# EFM32_G11_MCU.net
KiCad netlist of a schematic drawn in Altium Designer
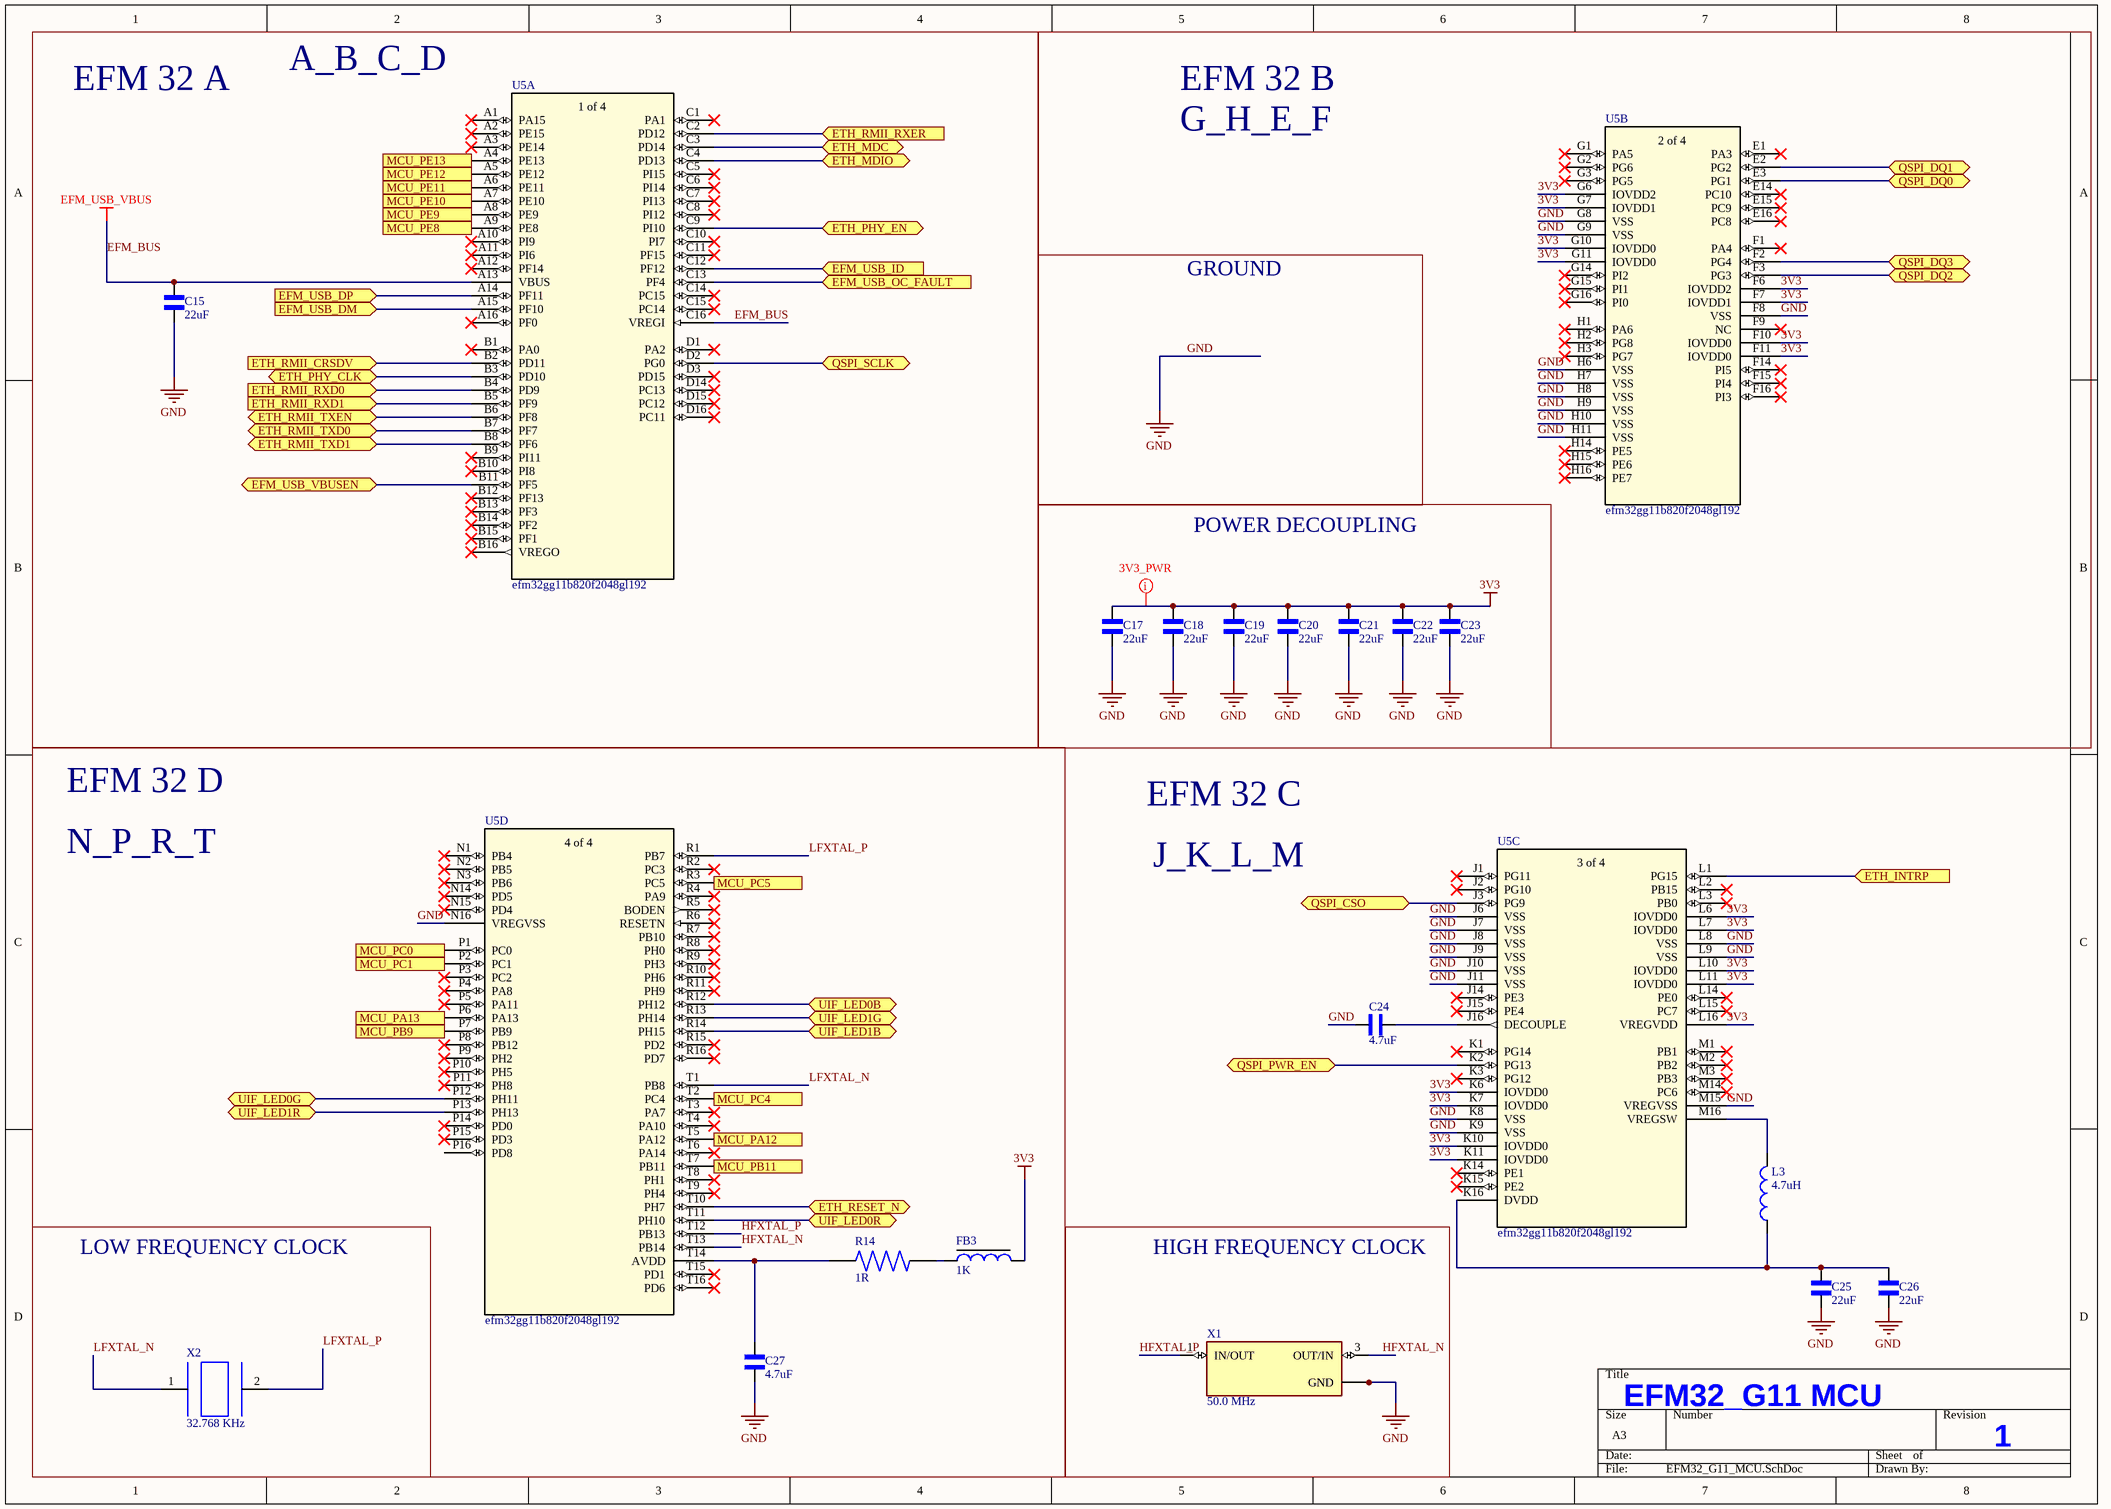
[diagram p0: EFM32_G11_MCU.SchDoc]

(export (version "E")
  (design (tool "Eeschema 10.0.6"))
  (components
    (comp (ref "C15")
      (value "22uF")
      (footprint "C0603")
      (description "0603 22 uF 10 V ±20% Tolerance X5R Surface Mount Multilayer Ceramic Capacitor")
      (fields
        (field (name "MANUFACTURER") "Murata")
        (field (name "MANUFACTURER PART NUMBER") "ZRB18AR61A226ME01L")
      )
      (libsource (lib "") (part "ZRB18AR61A226ME01L_1"))
    )
    (comp (ref "C17")
      (value "22uF")
      (footprint "C0603")
      (description "0603 22 uF 10 V ±20% Tolerance X5R Surface Mount Multilayer Ceramic Capacitor")
      (fields
        (field (name "MANUFACTURER") "Murata")
        (field (name "MANUFACTURER PART NUMBER") "ZRB18AR61A226ME01L")
      )
      (libsource (lib "") (part "ZRB18AR61A226ME01L_1"))
    )
    (comp (ref "C18")
      (value "22uF")
      (footprint "C0603")
      (description "0603 22 uF 10 V ±20% Tolerance X5R Surface Mount Multilayer Ceramic Capacitor")
      (fields
        (field (name "MANUFACTURER") "Murata")
        (field (name "MANUFACTURER PART NUMBER") "ZRB18AR61A226ME01L")
      )
      (libsource (lib "") (part "ZRB18AR61A226ME01L_1"))
    )
    (comp (ref "C19")
      (value "22uF")
      (footprint "C0603")
      (description "0603 22 uF 10 V ±20% Tolerance X5R Surface Mount Multilayer Ceramic Capacitor")
      (fields
        (field (name "MANUFACTURER") "Murata")
        (field (name "MANUFACTURER PART NUMBER") "ZRB18AR61A226ME01L")
      )
      (libsource (lib "nnts") (part "ZRB18AR61A226ME01L"))
    )
    (comp (ref "C20")
      (value "22uF")
      (footprint "C0603")
      (description "0603 22 uF 10 V ±20% Tolerance X5R Surface Mount Multilayer Ceramic Capacitor")
      (fields
        (field (name "MANUFACTURER") "Murata")
        (field (name "MANUFACTURER PART NUMBER") "ZRB18AR61A226ME01L")
      )
      (libsource (lib "nnts") (part "ZRB18AR61A226ME01L"))
    )
    (comp (ref "C21")
      (value "22uF")
      (footprint "C0603")
      (description "0603 22 uF 10 V ±20% Tolerance X5R Surface Mount Multilayer Ceramic Capacitor")
      (fields
        (field (name "MANUFACTURER") "Murata")
        (field (name "MANUFACTURER PART NUMBER") "ZRB18AR61A226ME01L")
      )
      (libsource (lib "nnts") (part "ZRB18AR61A226ME01L"))
    )
    (comp (ref "C22")
      (value "22uF")
      (footprint "C0603")
      (description "0603 22 uF 10 V ±20% Tolerance X5R Surface Mount Multilayer Ceramic Capacitor")
      (fields
        (field (name "MANUFACTURER") "Murata")
        (field (name "MANUFACTURER PART NUMBER") "ZRB18AR61A226ME01L")
      )
      (libsource (lib "nnts") (part "ZRB18AR61A226ME01L"))
    )
    (comp (ref "C23")
      (value "22uF")
      (footprint "C0603")
      (description "0603 22 uF 10 V ±20% Tolerance X5R Surface Mount Multilayer Ceramic Capacitor")
      (fields
        (field (name "MANUFACTURER") "Murata")
        (field (name "MANUFACTURER PART NUMBER") "ZRB18AR61A226ME01L")
      )
      (libsource (lib "nnts") (part "ZRB18AR61A226ME01L"))
    )
    (comp (ref "C24")
      (value "4.7uF")
      (footprint "C0603")
      (description "Cap Ceramic 4.7uF 10V X5R 10% Pad SMD 0603 85C T/R")
      (fields
        (field (name "MANUFACTURER") "Samsung")
        (field (name "MANUFACTURER PART NUMBER") "CL10A475KP8NNNC")
      )
      (libsource (lib "nnts") (part "CL10A475KP8NNNC"))
    )
    (comp (ref "C25")
      (value "22uF")
      (footprint "C0603")
      (description "0603 22 uF 10 V ±20% Tolerance X5R Surface Mount Multilayer Ceramic Capacitor")
      (fields
        (field (name "MANUFACTURER") "Murata")
        (field (name "MANUFACTURER PART NUMBER") "ZRB18AR61A226ME01L")
      )
      (libsource (lib "nnts") (part "ZRB18AR61A226ME01L"))
    )
    (comp (ref "C26")
      (value "22uF")
      (footprint "C0603")
      (description "0603 22 uF 10 V ±20% Tolerance X5R Surface Mount Multilayer Ceramic Capacitor")
      (fields
        (field (name "MANUFACTURER") "Murata")
        (field (name "MANUFACTURER PART NUMBER") "ZRB18AR61A226ME01L")
      )
      (libsource (lib "nnts") (part "ZRB18AR61A226ME01L"))
    )
    (comp (ref "C27")
      (value "4.7uF")
      (footprint "C0603")
      (description "Cap Ceramic 4.7uF 10V X5R 10% Pad SMD 0603 85C T/R")
      (fields
        (field (name "MANUFACTURER") "Samsung")
        (field (name "MANUFACTURER PART NUMBER") "CL10A475KP8NNNC")
      )
      (libsource (lib "") (part "CL10A475KP8NNNC_1"))
    )
    (comp (ref "FB3")
      (value "1K")
      (footprint "FB0402")
      (description "FERRITE BEAD 1 KOHM 0402 1LN")
      (fields
        (field (name "MANUFACTURER") "Murata")
        (field (name "MANUFACTURER PART NUMBER") "BLM15AG102SH1D")
      )
      (libsource (lib "nnts") (part "BLM15AG102SH1D"))
    )
    (comp (ref "L3")
      (value "4.7uH")
      (footprint "L0805")
      (description "Inductor with Inductance: 4.7uH Tol. +/-20%, Package: 0805 (2012)")
      (fields (field (name "MP") "LQM21PN4R7MGRB") (field (name "MF") "Murata"))
      (libsource (lib "nnts") (part "LQM21PN4R7MGRB"))
    )
    (comp (ref "R14")
      (value "1R")
      (footprint "R0402 Vishay")
      (description "RES SMD 1 OHM 1% 1/16W 0402")
      (fields
        (field (name "MANUFACTURER") "Vishay")
        (field (name "MANUFACTURER PART NUMBER") "CRCW04021R00FNED")
      )
      (libsource (lib "nnts") (part "CRCW04021R00FNED"))
    )
    (comp (ref "U5")
      (value "efm32gg11b820f2048gl192")
      (footprint "MCU_GG11")
      (description "No Description Available")
      (fields (field (name "COPYRIGHT") "Copyright (C) 2016 Accelerated Designs. All rights reserved"))
      (libsource (lib "nnts") (part "EFM32GG11B820F20"))
    )
    (comp (ref "X1")
      (value "50.0 MHz")
      (footprint "XTAL_ECS-500-8-47B-CWY-TR")
      (description "CRYSTAL 50.0000MHZ 8PF SMD")
      (fields (field (name "MF") "ECS Inc.") (field (name "MP") "ECS-500-8-47B-CWY-TR"))
      (libsource (lib "nnts") (part "ECS-500-8-47B-CWY-TR"))
    )
    (comp (ref "X2")
      (value "32.768 KHz")
      (footprint "XTAL_FC-135_32.7680KA-A0")
      (description "32.768kHz Â±20ppm Crystal 12.5pF 70 kOhms 2-SMD, No Lead")
      (fields (field (name "MP") "FC-135 32.7680KA-A0") (field (name "MF") "EPSON"))
      (libsource (lib "nnts") (part "FC-135_32.7680KA-A0"))
    )
  )
  (nets
    (net (code "1") (name "/EFM_USB_DM") (class "Default")
      (node (ref "U5") (pin "A15") (pinfunction "PF10_A15") (pintype "bidirectional"))
    )
    (net (code "2") (name "/EFM_USB_DP") (class "Default")
      (node (ref "U5") (pin "A14") (pinfunction "PF11_A14") (pintype "bidirectional"))
    )
    (net (code "3") (name "/EFM_USB_ID") (class "Default")
      (node (ref "U5") (pin "C12") (pinfunction "PF12_C12") (pintype "bidirectional"))
    )
    (net (code "4") (name "/EFM_USB_OC_FAULT") (class "Default")
      (node (ref "U5") (pin "C13") (pinfunction "PF4_C13") (pintype "bidirectional"))
    )
    (net (code "5") (name "/EFM_USB_VBUSEN") (class "Default")
      (node (ref "U5") (pin "B11") (pinfunction "PF5_B11") (pintype "bidirectional"))
    )
    (net (code "6") (name "/ETH_INTRP") (class "Default")
      (node (ref "U5") (pin "L1") (pinfunction "PG15_L1") (pintype "bidirectional"))
    )
    (net (code "7") (name "/ETH_MDC") (class "Default")
      (node (ref "U5") (pin "C3") (pinfunction "PD14_C3") (pintype "bidirectional"))
    )
    (net (code "8") (name "/ETH_MDIO") (class "Default")
      (node (ref "U5") (pin "C4") (pinfunction "PD13_C4") (pintype "bidirectional"))
    )
    (net (code "9") (name "/ETH_PHY_CLK") (class "Default")
      (node (ref "U5") (pin "B3") (pinfunction "PD10_B3") (pintype "bidirectional"))
    )
    (net (code "10") (name "/ETH_PHY_EN") (class "Default")
      (node (ref "U5") (pin "C9") (pinfunction "PI10_C9") (pintype "bidirectional"))
    )
    (net (code "11") (name "/ETH_RESET_N") (class "Default")
      (node (ref "U5") (pin "T10") (pinfunction "PH7_T10") (pintype "bidirectional"))
    )
    (net (code "12") (name "/ETH_RMII_CRSDV") (class "Default")
      (node (ref "U5") (pin "B2") (pinfunction "PD11_B2") (pintype "bidirectional"))
    )
    (net (code "13") (name "/ETH_RMII_RXD0") (class "Default")
      (node (ref "U5") (pin "B4") (pinfunction "PD9_B4") (pintype "bidirectional"))
    )
    (net (code "14") (name "/ETH_RMII_RXD1") (class "Default")
      (node (ref "U5") (pin "B5") (pinfunction "PF9_B5") (pintype "bidirectional"))
    )
    (net (code "15") (name "/ETH_RMII_RXER") (class "Default")
      (node (ref "U5") (pin "C2") (pinfunction "PD12_C2") (pintype "bidirectional"))
    )
    (net (code "16") (name "/ETH_RMII_TXD0") (class "Default")
      (node (ref "U5") (pin "B7") (pinfunction "PF7_B7") (pintype "bidirectional"))
    )
    (net (code "17") (name "/ETH_RMII_TXD1") (class "Default")
      (node (ref "U5") (pin "B8") (pinfunction "PF6_B8") (pintype "bidirectional"))
    )
    (net (code "18") (name "/ETH_RMII_TXEN") (class "Default")
      (node (ref "U5") (pin "B6") (pinfunction "PF8_B6") (pintype "bidirectional"))
    )
    (net (code "19") (name "/HFXTAL_N") (class "Default")
      (node (ref "U5") (pin "T13") (pinfunction "PB14_T13") (pintype "bidirectional"))
      (node (ref "X1") (pin "3") (pinfunction "OUT/IN_3") (pintype "bidirectional"))
    )
    (net (code "20") (name "/HFXTAL_P") (class "Default")
      (node (ref "U5") (pin "T12") (pinfunction "PB13_T12") (pintype "bidirectional"))
      (node (ref "X1") (pin "1") (pinfunction "IN/OUT_1") (pintype "bidirectional"))
    )
    (net (code "21") (name "/LFXTAL_N") (class "Default")
      (node (ref "U5") (pin "T1") (pinfunction "PB8_T1") (pintype "bidirectional"))
      (node (ref "X2") (pin "1") (pinfunction "1_1") (pintype "passive"))
    )
    (net (code "22") (name "/LFXTAL_P") (class "Default")
      (node (ref "U5") (pin "R1") (pinfunction "PB7_R1") (pintype "bidirectional"))
      (node (ref "X2") (pin "2") (pinfunction "2_2") (pintype "passive"))
    )
    (net (code "23") (name "/MCU_PA12") (class "Default")
      (node (ref "U5") (pin "T5") (pinfunction "PA12_T5") (pintype "bidirectional"))
    )
    (net (code "24") (name "/MCU_PA13") (class "Default")
      (node (ref "U5") (pin "P6") (pinfunction "PA13_P6") (pintype "bidirectional"))
    )
    (net (code "25") (name "/MCU_PB9") (class "Default")
      (node (ref "U5") (pin "P7") (pinfunction "PB9_P7") (pintype "bidirectional"))
    )
    (net (code "26") (name "/MCU_PB11") (class "Default")
      (node (ref "U5") (pin "T7") (pinfunction "PB11_T7") (pintype "bidirectional"))
    )
    (net (code "27") (name "/MCU_PC0") (class "Default")
      (node (ref "U5") (pin "P1") (pinfunction "PC0_P1") (pintype "bidirectional"))
    )
    (net (code "28") (name "/MCU_PC1") (class "Default")
      (node (ref "U5") (pin "P2") (pinfunction "PC1_P2") (pintype "bidirectional"))
    )
    (net (code "29") (name "/MCU_PC4") (class "Default")
      (node (ref "U5") (pin "T2") (pinfunction "PC4_T2") (pintype "bidirectional"))
    )
    (net (code "30") (name "/MCU_PC5") (class "Default")
      (node (ref "U5") (pin "R3") (pinfunction "PC5_R3") (pintype "bidirectional"))
    )
    (net (code "31") (name "/MCU_PE8") (class "Default")
      (node (ref "U5") (pin "A9") (pinfunction "PE8_A9") (pintype "bidirectional"))
    )
    (net (code "32") (name "/MCU_PE9") (class "Default")
      (node (ref "U5") (pin "A8") (pinfunction "PE9_A8") (pintype "bidirectional"))
    )
    (net (code "33") (name "/MCU_PE10") (class "Default")
      (node (ref "U5") (pin "A7") (pinfunction "PE10_A7") (pintype "bidirectional"))
    )
    (net (code "34") (name "/MCU_PE11") (class "Default")
      (node (ref "U5") (pin "A6") (pinfunction "PE11_A6") (pintype "bidirectional"))
    )
    (net (code "35") (name "/MCU_PE12") (class "Default")
      (node (ref "U5") (pin "A5") (pinfunction "PE12_A5") (pintype "bidirectional"))
    )
    (net (code "36") (name "/MCU_PE13") (class "Default")
      (node (ref "U5") (pin "A4") (pinfunction "PE13_A4") (pintype "bidirectional"))
    )
    (net (code "37") (name "/QSPI_CSO") (class "Default")
      (node (ref "U5") (pin "J3") (pinfunction "PG9_J3") (pintype "bidirectional"))
    )
    (net (code "38") (name "/QSPI_DQ0") (class "Default")
      (node (ref "U5") (pin "E3") (pinfunction "PG1_E3") (pintype "bidirectional"))
    )
    (net (code "39") (name "/QSPI_DQ1") (class "Default")
      (node (ref "U5") (pin "E2") (pinfunction "PG2_E2") (pintype "bidirectional"))
    )
    (net (code "40") (name "/QSPI_DQ2") (class "Default")
      (node (ref "U5") (pin "F3") (pinfunction "PG3_F3") (pintype "bidirectional"))
    )
    (net (code "41") (name "/QSPI_DQ3") (class "Default")
      (node (ref "U5") (pin "F2") (pinfunction "PG4_F2") (pintype "bidirectional"))
    )
    (net (code "42") (name "/QSPI_PWR_EN") (class "Default")
      (node (ref "U5") (pin "K2") (pinfunction "PG13_K2") (pintype "bidirectional"))
    )
    (net (code "43") (name "/QSPI_SCLK") (class "Default")
      (node (ref "U5") (pin "D2") (pinfunction "PG0_D2") (pintype "bidirectional"))
    )
    (net (code "44") (name "/UIF_LED0B") (class "Default")
      (node (ref "U5") (pin "R12") (pinfunction "PH12_R12") (pintype "bidirectional"))
    )
    (net (code "45") (name "/UIF_LED0G") (class "Default")
      (node (ref "U5") (pin "P12") (pinfunction "PH11_P12") (pintype "bidirectional"))
    )
    (net (code "46") (name "/UIF_LED0R") (class "Default")
      (node (ref "U5") (pin "T11") (pinfunction "PH10_T11") (pintype "bidirectional"))
    )
    (net (code "47") (name "/UIF_LED1B") (class "Default")
      (node (ref "U5") (pin "R14") (pinfunction "PH15_R14") (pintype "bidirectional"))
    )
    (net (code "48") (name "/UIF_LED1G") (class "Default")
      (node (ref "U5") (pin "R13") (pinfunction "PH14_R13") (pintype "bidirectional"))
    )
    (net (code "49") (name "/UIF_LED1R") (class "Default")
      (node (ref "U5") (pin "P13") (pinfunction "PH13_P13") (pintype "bidirectional"))
    )
    (net (code "50") (name "3V3") (class "Default")
      (node (ref "C17") (pin "2") (pinfunction "2_2") (pintype "passive"))
      (node (ref "C18") (pin "2") (pinfunction "2_2") (pintype "passive"))
      (node (ref "C19") (pin "1") (pinfunction "1_1") (pintype "passive"))
      (node (ref "C20") (pin "1") (pinfunction "1_1") (pintype "passive"))
      (node (ref "C21") (pin "1") (pinfunction "1_1") (pintype "passive"))
      (node (ref "C22") (pin "1") (pinfunction "1_1") (pintype "passive"))
      (node (ref "C23") (pin "1") (pinfunction "1_1") (pintype "passive"))
      (node (ref "FB3") (pin "2") (pinfunction "2_2") (pintype "passive"))
      (node (ref "U5") (pin "F10") (pinfunction "IOVDD0_F10") (pintype "power_in"))
      (node (ref "U5") (pin "F11") (pinfunction "IOVDD0_F11") (pintype "power_in"))
      (node (ref "U5") (pin "F6") (pinfunction "IOVDD2_F6") (pintype "power_in"))
      (node (ref "U5") (pin "F7") (pinfunction "IOVDD1_F7") (pintype "power_in"))
      (node (ref "U5") (pin "G10") (pinfunction "IOVDD0_G10") (pintype "power_in"))
      (node (ref "U5") (pin "G11") (pinfunction "IOVDD0_G11") (pintype "power_in"))
      (node (ref "U5") (pin "G6") (pinfunction "IOVDD2_G6") (pintype "power_in"))
      (node (ref "U5") (pin "G7") (pinfunction "IOVDD1_G7") (pintype "power_in"))
      (node (ref "U5") (pin "K10") (pinfunction "IOVDD0_K10") (pintype "power_in"))
      (node (ref "U5") (pin "K11") (pinfunction "IOVDD0_K11") (pintype "power_in"))
      (node (ref "U5") (pin "K6") (pinfunction "IOVDD0_K6") (pintype "power_in"))
      (node (ref "U5") (pin "K7") (pinfunction "IOVDD0_K7") (pintype "power_in"))
      (node (ref "U5") (pin "L10") (pinfunction "IOVDD0_L10") (pintype "power_in"))
      (node (ref "U5") (pin "L11") (pinfunction "IOVDD0_L11") (pintype "power_in"))
      (node (ref "U5") (pin "L16") (pinfunction "VREGVDD_L16") (pintype "power_in"))
      (node (ref "U5") (pin "L6") (pinfunction "IOVDD0_L6") (pintype "power_in"))
      (node (ref "U5") (pin "L7") (pinfunction "IOVDD0_L7") (pintype "power_in"))
    )
    (net (code "51") (name "EFM_USB_VBUS") (class "Default")
      (node (ref "C15") (pin "2") (pinfunction "2_2") (pintype "passive"))
      (node (ref "U5") (pin "A13") (pinfunction "VBUS_A13") (pintype "power_in"))
      (node (ref "U5") (pin "C16") (pinfunction "VREGI_C16") (pintype "input"))
    )
    (net (code "52") (name "GND") (class "Default")
      (node (ref "C15") (pin "1") (pinfunction "1_1") (pintype "passive"))
      (node (ref "C17") (pin "1") (pinfunction "1_1") (pintype "passive"))
      (node (ref "C18") (pin "1") (pinfunction "1_1") (pintype "passive"))
      (node (ref "C19") (pin "2") (pinfunction "2_2") (pintype "passive"))
      (node (ref "C20") (pin "2") (pinfunction "2_2") (pintype "passive"))
      (node (ref "C21") (pin "2") (pinfunction "2_2") (pintype "passive"))
      (node (ref "C22") (pin "2") (pinfunction "2_2") (pintype "passive"))
      (node (ref "C23") (pin "2") (pinfunction "2_2") (pintype "passive"))
      (node (ref "C24") (pin "1") (pinfunction "1_1") (pintype "passive"))
      (node (ref "C25") (pin "2") (pinfunction "2_2") (pintype "passive"))
      (node (ref "C26") (pin "2") (pinfunction "2_2") (pintype "passive"))
      (node (ref "C27") (pin "1") (pinfunction "1_1") (pintype "passive"))
      (node (ref "U5") (pin "F8") (pinfunction "VSS_F8") (pintype "power_in"))
      (node (ref "U5") (pin "G8") (pinfunction "VSS_G8") (pintype "power_in"))
      (node (ref "U5") (pin "G9") (pinfunction "VSS_G9") (pintype "power_in"))
      (node (ref "U5") (pin "H10") (pinfunction "VSS_H10") (pintype "power_in"))
      (node (ref "U5") (pin "H11") (pinfunction "VSS_H11") (pintype "power_in"))
      (node (ref "U5") (pin "H6") (pinfunction "VSS_H6") (pintype "power_in"))
      (node (ref "U5") (pin "H7") (pinfunction "VSS_H7") (pintype "power_in"))
      (node (ref "U5") (pin "H8") (pinfunction "VSS_H8") (pintype "power_in"))
      (node (ref "U5") (pin "H9") (pinfunction "VSS_H9") (pintype "power_in"))
      (node (ref "U5") (pin "J10") (pinfunction "VSS_J10") (pintype "power_in"))
      (node (ref "U5") (pin "J11") (pinfunction "VSS_J11") (pintype "power_in"))
      (node (ref "U5") (pin "J6") (pinfunction "VSS_J6") (pintype "power_in"))
      (node (ref "U5") (pin "J7") (pinfunction "VSS_J7") (pintype "power_in"))
      (node (ref "U5") (pin "J8") (pinfunction "VSS_J8") (pintype "power_in"))
      (node (ref "U5") (pin "J9") (pinfunction "VSS_J9") (pintype "power_in"))
      (node (ref "U5") (pin "K8") (pinfunction "VSS_K8") (pintype "power_in"))
      (node (ref "U5") (pin "K9") (pinfunction "VSS_K9") (pintype "power_in"))
      (node (ref "U5") (pin "L8") (pinfunction "VSS_L8") (pintype "power_in"))
      (node (ref "U5") (pin "L9") (pinfunction "VSS_L9") (pintype "power_in"))
      (node (ref "U5") (pin "M15") (pinfunction "VREGVSS_M15") (pintype "power_in"))
      (node (ref "U5") (pin "N16") (pinfunction "VREGVSS_N16") (pintype "power_in"))
      (node (ref "X1") (pin "2") (pinfunction "GND_2") (pintype "power_in"))
      (node (ref "X1") (pin "4") (pinfunction "GND_4") (pintype "power_in"))
    )
    (net (code "53") (name "Net-(FB3-Pad1)") (class "Default")
      (node (ref "FB3") (pin "1") (pinfunction "1_1") (pintype "passive"))
      (node (ref "R14") (pin "2") (pinfunction "2_2") (pintype "passive"))
    )
    (net (code "54") (name "Net-(U5C-DECOUPLE)") (class "Default")
      (node (ref "C24") (pin "2") (pinfunction "2_2") (pintype "passive"))
      (node (ref "U5") (pin "J16") (pinfunction "DECOUPLE_J16") (pintype "output"))
    )
    (net (code "55") (name "Net-(U5C-DVDD)") (class "Default")
      (node (ref "C25") (pin "1") (pinfunction "1_1") (pintype "passive"))
      (node (ref "C26") (pin "1") (pinfunction "1_1") (pintype "passive"))
      (node (ref "L3") (pin "1") (pinfunction "1_1") (pintype "passive"))
      (node (ref "U5") (pin "K16") (pinfunction "DVDD_K16") (pintype "power_in"))
    )
    (net (code "56") (name "Net-(U5C-VREGSW)") (class "Default")
      (node (ref "L3") (pin "2") (pinfunction "2_2") (pintype "passive"))
      (node (ref "U5") (pin "M16") (pinfunction "VREGSW_M16") (pintype "power_in"))
    )
    (net (code "57") (name "Net-(U5D-AVDD)") (class "Default")
      (node (ref "C27") (pin "2") (pinfunction "2_2") (pintype "passive"))
      (node (ref "R14") (pin "1") (pinfunction "1_1") (pintype "passive"))
      (node (ref "U5") (pin "T14") (pinfunction "AVDD_T14") (pintype "power_in"))
    )
    (net (code "58") (name "unconnected-(U5A-PA0-PadB1)") (class "Default")
      (node (ref "U5") (pin "B1") (pinfunction "PA0_B1") (pintype "bidirectional+no_connect"))
    )
    (net (code "59") (name "unconnected-(U5A-PA1-PadC1)") (class "Default")
      (node (ref "U5") (pin "C1") (pinfunction "PA1_C1") (pintype "bidirectional+no_connect"))
    )
    (net (code "60") (name "unconnected-(U5A-PA2-PadD1)") (class "Default")
      (node (ref "U5") (pin "D1") (pinfunction "PA2_D1") (pintype "bidirectional+no_connect"))
    )
    (net (code "61") (name "unconnected-(U5A-PA15-PadA1)") (class "Default")
      (node (ref "U5") (pin "A1") (pinfunction "PA15_A1") (pintype "bidirectional+no_connect"))
    )
    (net (code "62") (name "unconnected-(U5A-PC11-PadD16)") (class "Default")
      (node (ref "U5") (pin "D16") (pinfunction "PC11_D16") (pintype "bidirectional+no_connect"))
    )
    (net (code "63") (name "unconnected-(U5A-PC12-PadD15)") (class "Default")
      (node (ref "U5") (pin "D15") (pinfunction "PC12_D15") (pintype "bidirectional+no_connect"))
    )
    (net (code "64") (name "unconnected-(U5A-PC13-PadD14)") (class "Default")
      (node (ref "U5") (pin "D14") (pinfunction "PC13_D14") (pintype "bidirectional+no_connect"))
    )
    (net (code "65") (name "unconnected-(U5A-PC14-PadC15)") (class "Default")
      (node (ref "U5") (pin "C15") (pinfunction "PC14_C15") (pintype "bidirectional+no_connect"))
    )
    (net (code "66") (name "unconnected-(U5A-PC15-PadC14)") (class "Default")
      (node (ref "U5") (pin "C14") (pinfunction "PC15_C14") (pintype "bidirectional+no_connect"))
    )
    (net (code "67") (name "unconnected-(U5A-PD15-PadD3)") (class "Default")
      (node (ref "U5") (pin "D3") (pinfunction "PD15_D3") (pintype "bidirectional+no_connect"))
    )
    (net (code "68") (name "unconnected-(U5A-PE14-PadA3)") (class "Default")
      (node (ref "U5") (pin "A3") (pinfunction "PE14_A3") (pintype "bidirectional+no_connect"))
    )
    (net (code "69") (name "unconnected-(U5A-PE15-PadA2)") (class "Default")
      (node (ref "U5") (pin "A2") (pinfunction "PE15_A2") (pintype "bidirectional+no_connect"))
    )
    (net (code "70") (name "unconnected-(U5A-PF0-PadA16)") (class "Default")
      (node (ref "U5") (pin "A16") (pinfunction "PF0_A16") (pintype "bidirectional+no_connect"))
    )
    (net (code "71") (name "unconnected-(U5A-PF1-PadB15)") (class "Default")
      (node (ref "U5") (pin "B15") (pinfunction "PF1_B15") (pintype "bidirectional+no_connect"))
    )
    (net (code "72") (name "unconnected-(U5A-PF2-PadB14)") (class "Default")
      (node (ref "U5") (pin "B14") (pinfunction "PF2_B14") (pintype "bidirectional+no_connect"))
    )
    (net (code "73") (name "unconnected-(U5A-PF3-PadB13)") (class "Default")
      (node (ref "U5") (pin "B13") (pinfunction "PF3_B13") (pintype "bidirectional+no_connect"))
    )
    (net (code "74") (name "unconnected-(U5A-PF13-PadB12)") (class "Default")
      (node (ref "U5") (pin "B12") (pinfunction "PF13_B12") (pintype "bidirectional+no_connect"))
    )
    (net (code "75") (name "unconnected-(U5A-PF14-PadA12)") (class "Default")
      (node (ref "U5") (pin "A12") (pinfunction "PF14_A12") (pintype "bidirectional+no_connect"))
    )
    (net (code "76") (name "unconnected-(U5A-PF15-PadC11)") (class "Default")
      (node (ref "U5") (pin "C11") (pinfunction "PF15_C11") (pintype "bidirectional+no_connect"))
    )
    (net (code "77") (name "unconnected-(U5A-PI6-PadA11)") (class "Default")
      (node (ref "U5") (pin "A11") (pinfunction "PI6_A11") (pintype "bidirectional+no_connect"))
    )
    (net (code "78") (name "unconnected-(U5A-PI7-PadC10)") (class "Default")
      (node (ref "U5") (pin "C10") (pinfunction "PI7_C10") (pintype "bidirectional+no_connect"))
    )
    (net (code "79") (name "unconnected-(U5A-PI8-PadB10)") (class "Default")
      (node (ref "U5") (pin "B10") (pinfunction "PI8_B10") (pintype "bidirectional+no_connect"))
    )
    (net (code "80") (name "unconnected-(U5A-PI9-PadA10)") (class "Default")
      (node (ref "U5") (pin "A10") (pinfunction "PI9_A10") (pintype "bidirectional+no_connect"))
    )
    (net (code "81") (name "unconnected-(U5A-PI11-PadB9)") (class "Default")
      (node (ref "U5") (pin "B9") (pinfunction "PI11_B9") (pintype "bidirectional+no_connect"))
    )
    (net (code "82") (name "unconnected-(U5A-PI12-PadC8)") (class "Default")
      (node (ref "U5") (pin "C8") (pinfunction "PI12_C8") (pintype "bidirectional+no_connect"))
    )
    (net (code "83") (name "unconnected-(U5A-PI13-PadC7)") (class "Default")
      (node (ref "U5") (pin "C7") (pinfunction "PI13_C7") (pintype "bidirectional+no_connect"))
    )
    (net (code "84") (name "unconnected-(U5A-PI14-PadC6)") (class "Default")
      (node (ref "U5") (pin "C6") (pinfunction "PI14_C6") (pintype "bidirectional+no_connect"))
    )
    (net (code "85") (name "unconnected-(U5A-PI15-PadC5)") (class "Default")
      (node (ref "U5") (pin "C5") (pinfunction "PI15_C5") (pintype "bidirectional+no_connect"))
    )
    (net (code "86") (name "unconnected-(U5A-VREGO-PadB16)") (class "Default")
      (node (ref "U5") (pin "B16") (pinfunction "VREGO_B16") (pintype "output+no_connect"))
    )
    (net (code "87") (name "unconnected-(U5B-NC-PadF9)") (class "Default")
      (node (ref "U5") (pin "F9") (pinfunction "NC_F9") (pintype "passive+no_connect"))
    )
    (net (code "88") (name "unconnected-(U5B-PA3-PadE1)") (class "Default")
      (node (ref "U5") (pin "E1") (pinfunction "PA3_E1") (pintype "bidirectional+no_connect"))
    )
    (net (code "89") (name "unconnected-(U5B-PA4-PadF1)") (class "Default")
      (node (ref "U5") (pin "F1") (pinfunction "PA4_F1") (pintype "bidirectional+no_connect"))
    )
    (net (code "90") (name "unconnected-(U5B-PA5-PadG1)") (class "Default")
      (node (ref "U5") (pin "G1") (pinfunction "PA5_G1") (pintype "bidirectional+no_connect"))
    )
    (net (code "91") (name "unconnected-(U5B-PA6-PadH1)") (class "Default")
      (node (ref "U5") (pin "H1") (pinfunction "PA6_H1") (pintype "bidirectional+no_connect"))
    )
    (net (code "92") (name "unconnected-(U5B-PC8-PadE16)") (class "Default")
      (node (ref "U5") (pin "E16") (pinfunction "PC8_E16") (pintype "bidirectional+no_connect"))
    )
    (net (code "93") (name "unconnected-(U5B-PC9-PadE15)") (class "Default")
      (node (ref "U5") (pin "E15") (pinfunction "PC9_E15") (pintype "bidirectional+no_connect"))
    )
    (net (code "94") (name "unconnected-(U5B-PC10-PadE14)") (class "Default")
      (node (ref "U5") (pin "E14") (pinfunction "PC10_E14") (pintype "bidirectional+no_connect"))
    )
    (net (code "95") (name "unconnected-(U5B-PE5-PadH14)") (class "Default")
      (node (ref "U5") (pin "H14") (pinfunction "PE5_H14") (pintype "bidirectional+no_connect"))
    )
    (net (code "96") (name "unconnected-(U5B-PE6-PadH15)") (class "Default")
      (node (ref "U5") (pin "H15") (pinfunction "PE6_H15") (pintype "bidirectional+no_connect"))
    )
    (net (code "97") (name "unconnected-(U5B-PE7-PadH16)") (class "Default")
      (node (ref "U5") (pin "H16") (pinfunction "PE7_H16") (pintype "bidirectional+no_connect"))
    )
    (net (code "98") (name "unconnected-(U5B-PG5-PadG3)") (class "Default")
      (node (ref "U5") (pin "G3") (pinfunction "PG5_G3") (pintype "bidirectional+no_connect"))
    )
    (net (code "99") (name "unconnected-(U5B-PG6-PadG2)") (class "Default")
      (node (ref "U5") (pin "G2") (pinfunction "PG6_G2") (pintype "bidirectional+no_connect"))
    )
    (net (code "100") (name "unconnected-(U5B-PG7-PadH3)") (class "Default")
      (node (ref "U5") (pin "H3") (pinfunction "PG7_H3") (pintype "bidirectional+no_connect"))
    )
    (net (code "101") (name "unconnected-(U5B-PG8-PadH2)") (class "Default")
      (node (ref "U5") (pin "H2") (pinfunction "PG8_H2") (pintype "bidirectional+no_connect"))
    )
    (net (code "102") (name "unconnected-(U5B-PI0-PadG16)") (class "Default")
      (node (ref "U5") (pin "G16") (pinfunction "PI0_G16") (pintype "bidirectional+no_connect"))
    )
    (net (code "103") (name "unconnected-(U5B-PI1-PadG15)") (class "Default")
      (node (ref "U5") (pin "G15") (pinfunction "PI1_G15") (pintype "bidirectional+no_connect"))
    )
    (net (code "104") (name "unconnected-(U5B-PI2-PadG14)") (class "Default")
      (node (ref "U5") (pin "G14") (pinfunction "PI2_G14") (pintype "bidirectional+no_connect"))
    )
    (net (code "105") (name "unconnected-(U5B-PI3-PadF16)") (class "Default")
      (node (ref "U5") (pin "F16") (pinfunction "PI3_F16") (pintype "bidirectional+no_connect"))
    )
    (net (code "106") (name "unconnected-(U5B-PI4-PadF15)") (class "Default")
      (node (ref "U5") (pin "F15") (pinfunction "PI4_F15") (pintype "bidirectional+no_connect"))
    )
    (net (code "107") (name "unconnected-(U5B-PI5-PadF14)") (class "Default")
      (node (ref "U5") (pin "F14") (pinfunction "PI5_F14") (pintype "bidirectional+no_connect"))
    )
    (net (code "108") (name "unconnected-(U5C-PB0-PadL3)") (class "Default")
      (node (ref "U5") (pin "L3") (pinfunction "PB0_L3") (pintype "bidirectional+no_connect"))
    )
    (net (code "109") (name "unconnected-(U5C-PB1-PadM1)") (class "Default")
      (node (ref "U5") (pin "M1") (pinfunction "PB1_M1") (pintype "bidirectional+no_connect"))
    )
    (net (code "110") (name "unconnected-(U5C-PB2-PadM2)") (class "Default")
      (node (ref "U5") (pin "M2") (pinfunction "PB2_M2") (pintype "bidirectional+no_connect"))
    )
    (net (code "111") (name "unconnected-(U5C-PB3-PadM3)") (class "Default")
      (node (ref "U5") (pin "M3") (pinfunction "PB3_M3") (pintype "bidirectional+no_connect"))
    )
    (net (code "112") (name "unconnected-(U5C-PB15-PadL2)") (class "Default")
      (node (ref "U5") (pin "L2") (pinfunction "PB15_L2") (pintype "bidirectional+no_connect"))
    )
    (net (code "113") (name "unconnected-(U5C-PC6-PadM14)") (class "Default")
      (node (ref "U5") (pin "M14") (pinfunction "PC6_M14") (pintype "bidirectional+no_connect"))
    )
    (net (code "114") (name "unconnected-(U5C-PC7-PadL15)") (class "Default")
      (node (ref "U5") (pin "L15") (pinfunction "PC7_L15") (pintype "bidirectional+no_connect"))
    )
    (net (code "115") (name "unconnected-(U5C-PE0-PadL14)") (class "Default")
      (node (ref "U5") (pin "L14") (pinfunction "PE0_L14") (pintype "bidirectional+no_connect"))
    )
    (net (code "116") (name "unconnected-(U5C-PE1-PadK14)") (class "Default")
      (node (ref "U5") (pin "K14") (pinfunction "PE1_K14") (pintype "bidirectional+no_connect"))
    )
    (net (code "117") (name "unconnected-(U5C-PE2-PadK15)") (class "Default")
      (node (ref "U5") (pin "K15") (pinfunction "PE2_K15") (pintype "bidirectional+no_connect"))
    )
    (net (code "118") (name "unconnected-(U5C-PE3-PadJ14)") (class "Default")
      (node (ref "U5") (pin "J14") (pinfunction "PE3_J14") (pintype "bidirectional+no_connect"))
    )
    (net (code "119") (name "unconnected-(U5C-PE4-PadJ15)") (class "Default")
      (node (ref "U5") (pin "J15") (pinfunction "PE4_J15") (pintype "bidirectional+no_connect"))
    )
    (net (code "120") (name "unconnected-(U5C-PG10-PadJ2)") (class "Default")
      (node (ref "U5") (pin "J2") (pinfunction "PG10_J2") (pintype "bidirectional+no_connect"))
    )
    (net (code "121") (name "unconnected-(U5C-PG11-PadJ1)") (class "Default")
      (node (ref "U5") (pin "J1") (pinfunction "PG11_J1") (pintype "bidirectional+no_connect"))
    )
    (net (code "122") (name "unconnected-(U5C-PG12-PadK3)") (class "Default")
      (node (ref "U5") (pin "K3") (pinfunction "PG12_K3") (pintype "bidirectional+no_connect"))
    )
    (net (code "123") (name "unconnected-(U5C-PG14-PadK1)") (class "Default")
      (node (ref "U5") (pin "K1") (pinfunction "PG14_K1") (pintype "bidirectional+no_connect"))
    )
    (net (code "124") (name "unconnected-(U5D-BODEN-PadR5)") (class "Default")
      (node (ref "U5") (pin "R5") (pinfunction "BODEN_R5") (pintype "output+no_connect"))
    )
    (net (code "125") (name "unconnected-(U5D-PA7-PadT3)") (class "Default")
      (node (ref "U5") (pin "T3") (pinfunction "PA7_T3") (pintype "bidirectional+no_connect"))
    )
    (net (code "126") (name "unconnected-(U5D-PA8-PadP4)") (class "Default")
      (node (ref "U5") (pin "P4") (pinfunction "PA8_P4") (pintype "bidirectional+no_connect"))
    )
    (net (code "127") (name "unconnected-(U5D-PA9-PadR4)") (class "Default")
      (node (ref "U5") (pin "R4") (pinfunction "PA9_R4") (pintype "bidirectional+no_connect"))
    )
    (net (code "128") (name "unconnected-(U5D-PA10-PadT4)") (class "Default")
      (node (ref "U5") (pin "T4") (pinfunction "PA10_T4") (pintype "bidirectional+no_connect"))
    )
    (net (code "129") (name "unconnected-(U5D-PA11-PadP5)") (class "Default")
      (node (ref "U5") (pin "P5") (pinfunction "PA11_P5") (pintype "bidirectional+no_connect"))
    )
    (net (code "130") (name "unconnected-(U5D-PA14-PadT6)") (class "Default")
      (node (ref "U5") (pin "T6") (pinfunction "PA14_T6") (pintype "bidirectional+no_connect"))
    )
    (net (code "131") (name "unconnected-(U5D-PB4-PadN1)") (class "Default")
      (node (ref "U5") (pin "N1") (pinfunction "PB4_N1") (pintype "bidirectional+no_connect"))
    )
    (net (code "132") (name "unconnected-(U5D-PB5-PadN2)") (class "Default")
      (node (ref "U5") (pin "N2") (pinfunction "PB5_N2") (pintype "bidirectional+no_connect"))
    )
    (net (code "133") (name "unconnected-(U5D-PB6-PadN3)") (class "Default")
      (node (ref "U5") (pin "N3") (pinfunction "PB6_N3") (pintype "bidirectional+no_connect"))
    )
    (net (code "134") (name "unconnected-(U5D-PB10-PadR7)") (class "Default")
      (node (ref "U5") (pin "R7") (pinfunction "PB10_R7") (pintype "bidirectional+no_connect"))
    )
    (net (code "135") (name "unconnected-(U5D-PB12-PadP8)") (class "Default")
      (node (ref "U5") (pin "P8") (pinfunction "PB12_P8") (pintype "bidirectional+no_connect"))
    )
    (net (code "136") (name "unconnected-(U5D-PC2-PadP3)") (class "Default")
      (node (ref "U5") (pin "P3") (pinfunction "PC2_P3") (pintype "bidirectional+no_connect"))
    )
    (net (code "137") (name "unconnected-(U5D-PC3-PadR2)") (class "Default")
      (node (ref "U5") (pin "R2") (pinfunction "PC3_R2") (pintype "bidirectional+no_connect"))
    )
    (net (code "138") (name "unconnected-(U5D-PD0-PadP14)") (class "Default")
      (node (ref "U5") (pin "P14") (pinfunction "PD0_P14") (pintype "bidirectional+no_connect"))
    )
    (net (code "139") (name "unconnected-(U5D-PD1-PadT15)") (class "Default")
      (node (ref "U5") (pin "T15") (pinfunction "PD1_T15") (pintype "bidirectional+no_connect"))
    )
    (net (code "140") (name "unconnected-(U5D-PD2-PadR15)") (class "Default")
      (node (ref "U5") (pin "R15") (pinfunction "PD2_R15") (pintype "bidirectional+no_connect"))
    )
    (net (code "141") (name "unconnected-(U5D-PD3-PadP15)") (class "Default")
      (node (ref "U5") (pin "P15") (pinfunction "PD3_P15") (pintype "bidirectional+no_connect"))
    )
    (net (code "142") (name "unconnected-(U5D-PD4-PadN15)") (class "Default")
      (node (ref "U5") (pin "N15") (pinfunction "PD4_N15") (pintype "bidirectional+no_connect"))
    )
    (net (code "143") (name "unconnected-(U5D-PD5-PadN14)") (class "Default")
      (node (ref "U5") (pin "N14") (pinfunction "PD5_N14") (pintype "bidirectional+no_connect"))
    )
    (net (code "144") (name "unconnected-(U5D-PD6-PadT16)") (class "Default")
      (node (ref "U5") (pin "T16") (pinfunction "PD6_T16") (pintype "bidirectional+no_connect"))
    )
    (net (code "145") (name "unconnected-(U5D-PD7-PadR16)") (class "Default")
      (node (ref "U5") (pin "R16") (pinfunction "PD7_R16") (pintype "bidirectional+no_connect"))
    )
    (net (code "146") (name "unconnected-(U5D-PD8-PadP16)") (class "Default")
      (node (ref "U5") (pin "P16") (pinfunction "PD8_P16") (pintype "bidirectional"))
    )
    (net (code "147") (name "unconnected-(U5D-PH0-PadR8)") (class "Default")
      (node (ref "U5") (pin "R8") (pinfunction "PH0_R8") (pintype "bidirectional+no_connect"))
    )
    (net (code "148") (name "unconnected-(U5D-PH1-PadT8)") (class "Default")
      (node (ref "U5") (pin "T8") (pinfunction "PH1_T8") (pintype "bidirectional+no_connect"))
    )
    (net (code "149") (name "unconnected-(U5D-PH2-PadP9)") (class "Default")
      (node (ref "U5") (pin "P9") (pinfunction "PH2_P9") (pintype "bidirectional+no_connect"))
    )
    (net (code "150") (name "unconnected-(U5D-PH3-PadR9)") (class "Default")
      (node (ref "U5") (pin "R9") (pinfunction "PH3_R9") (pintype "bidirectional+no_connect"))
    )
    (net (code "151") (name "unconnected-(U5D-PH4-PadT9)") (class "Default")
      (node (ref "U5") (pin "T9") (pinfunction "PH4_T9") (pintype "bidirectional+no_connect"))
    )
    (net (code "152") (name "unconnected-(U5D-PH5-PadP10)") (class "Default")
      (node (ref "U5") (pin "P10") (pinfunction "PH5_P10") (pintype "bidirectional+no_connect"))
    )
    (net (code "153") (name "unconnected-(U5D-PH6-PadR10)") (class "Default")
      (node (ref "U5") (pin "R10") (pinfunction "PH6_R10") (pintype "bidirectional+no_connect"))
    )
    (net (code "154") (name "unconnected-(U5D-PH8-PadP11)") (class "Default")
      (node (ref "U5") (pin "P11") (pinfunction "PH8_P11") (pintype "bidirectional+no_connect"))
    )
    (net (code "155") (name "unconnected-(U5D-PH9-PadR11)") (class "Default")
      (node (ref "U5") (pin "R11") (pinfunction "PH9_R11") (pintype "bidirectional+no_connect"))
    )
    (net (code "156") (name "unconnected-(U5D-RESETN-PadR6)") (class "Default")
      (node (ref "U5") (pin "R6") (pinfunction "RESETN_R6") (pintype "input+no_connect"))
    )
  )
)
